# Anemometer.net
KiCad netlist of a schematic drawn in EAGLE
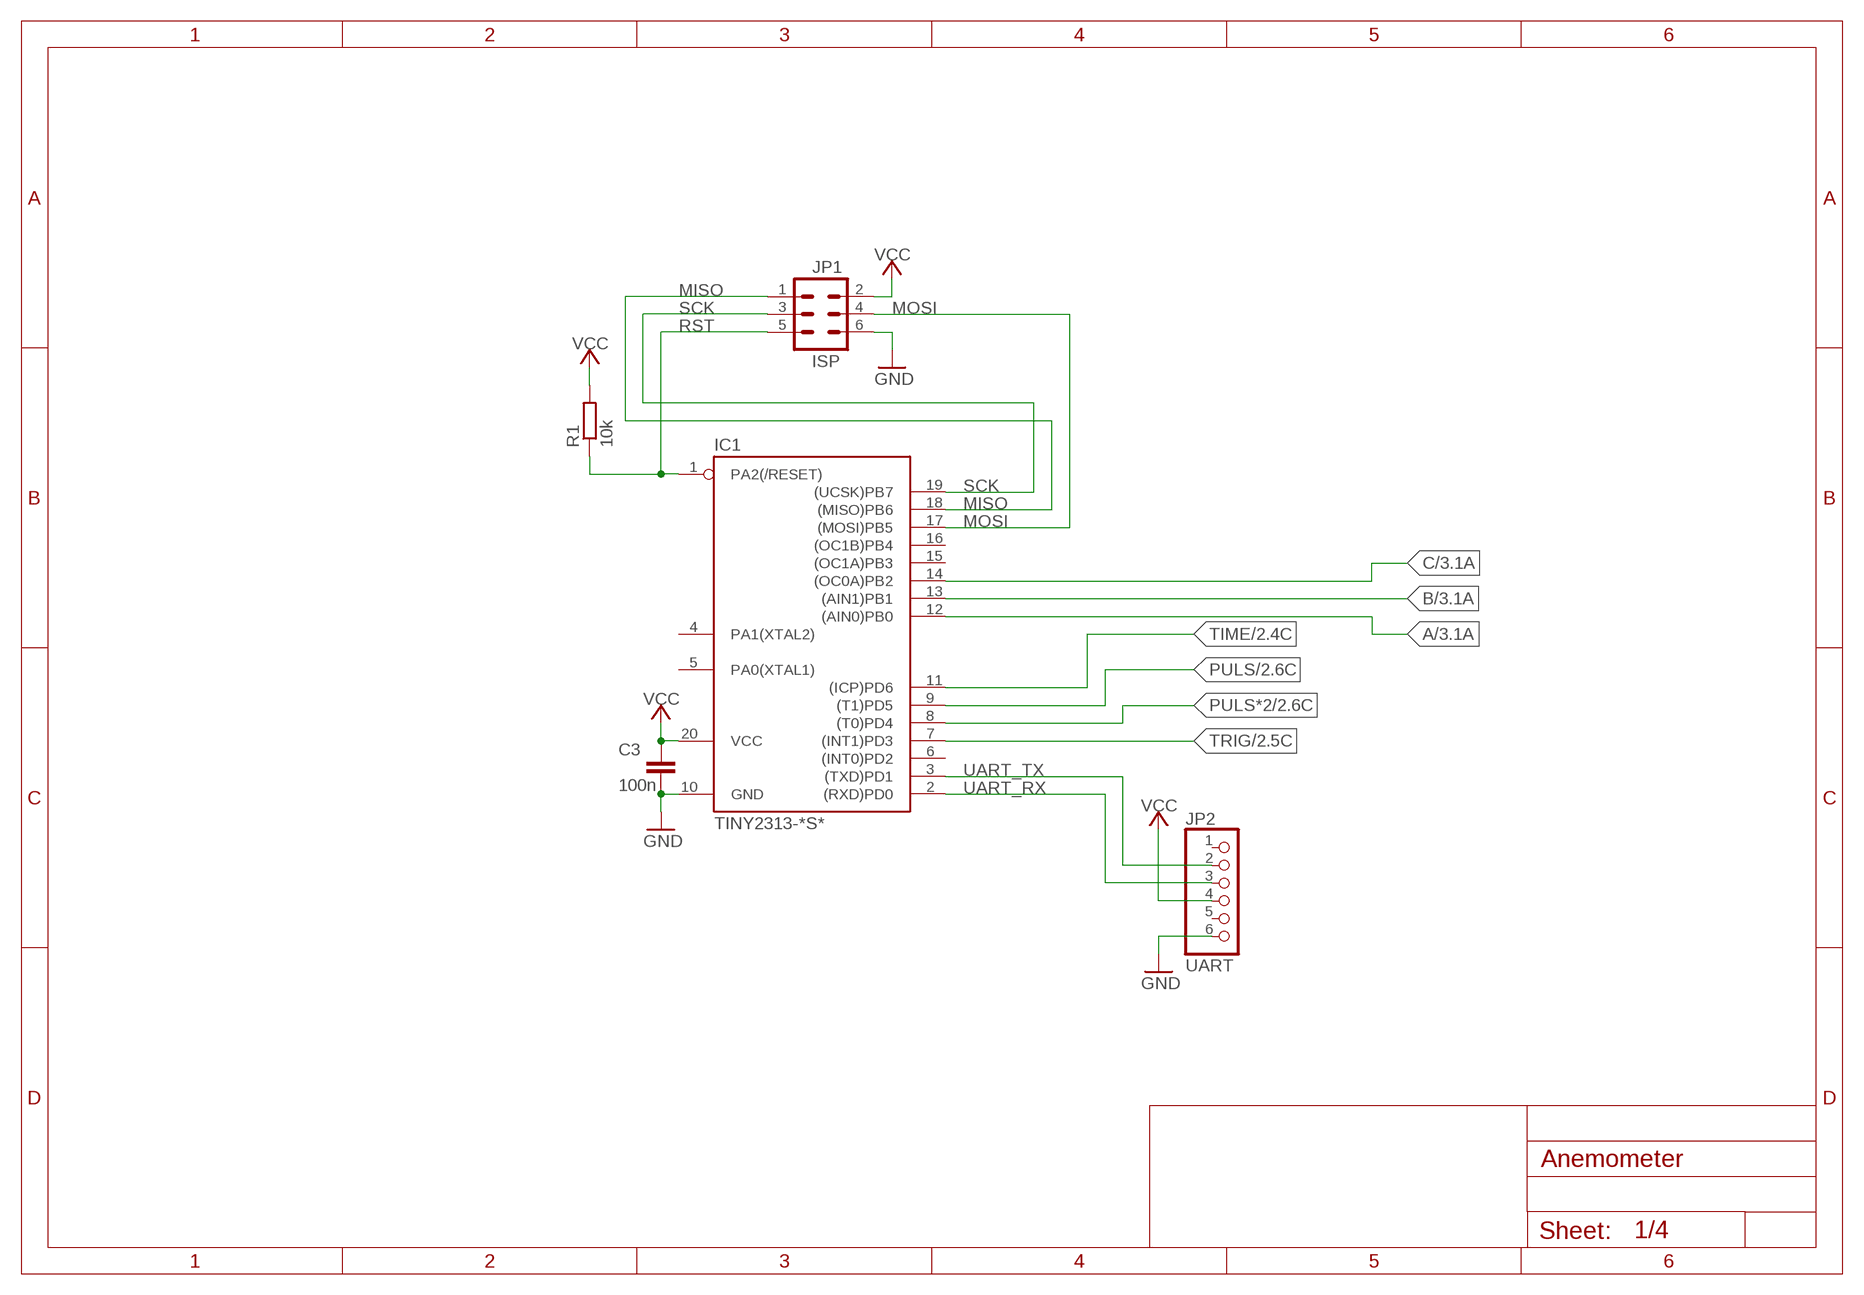
[diagram p0: schematic, sheet 1]
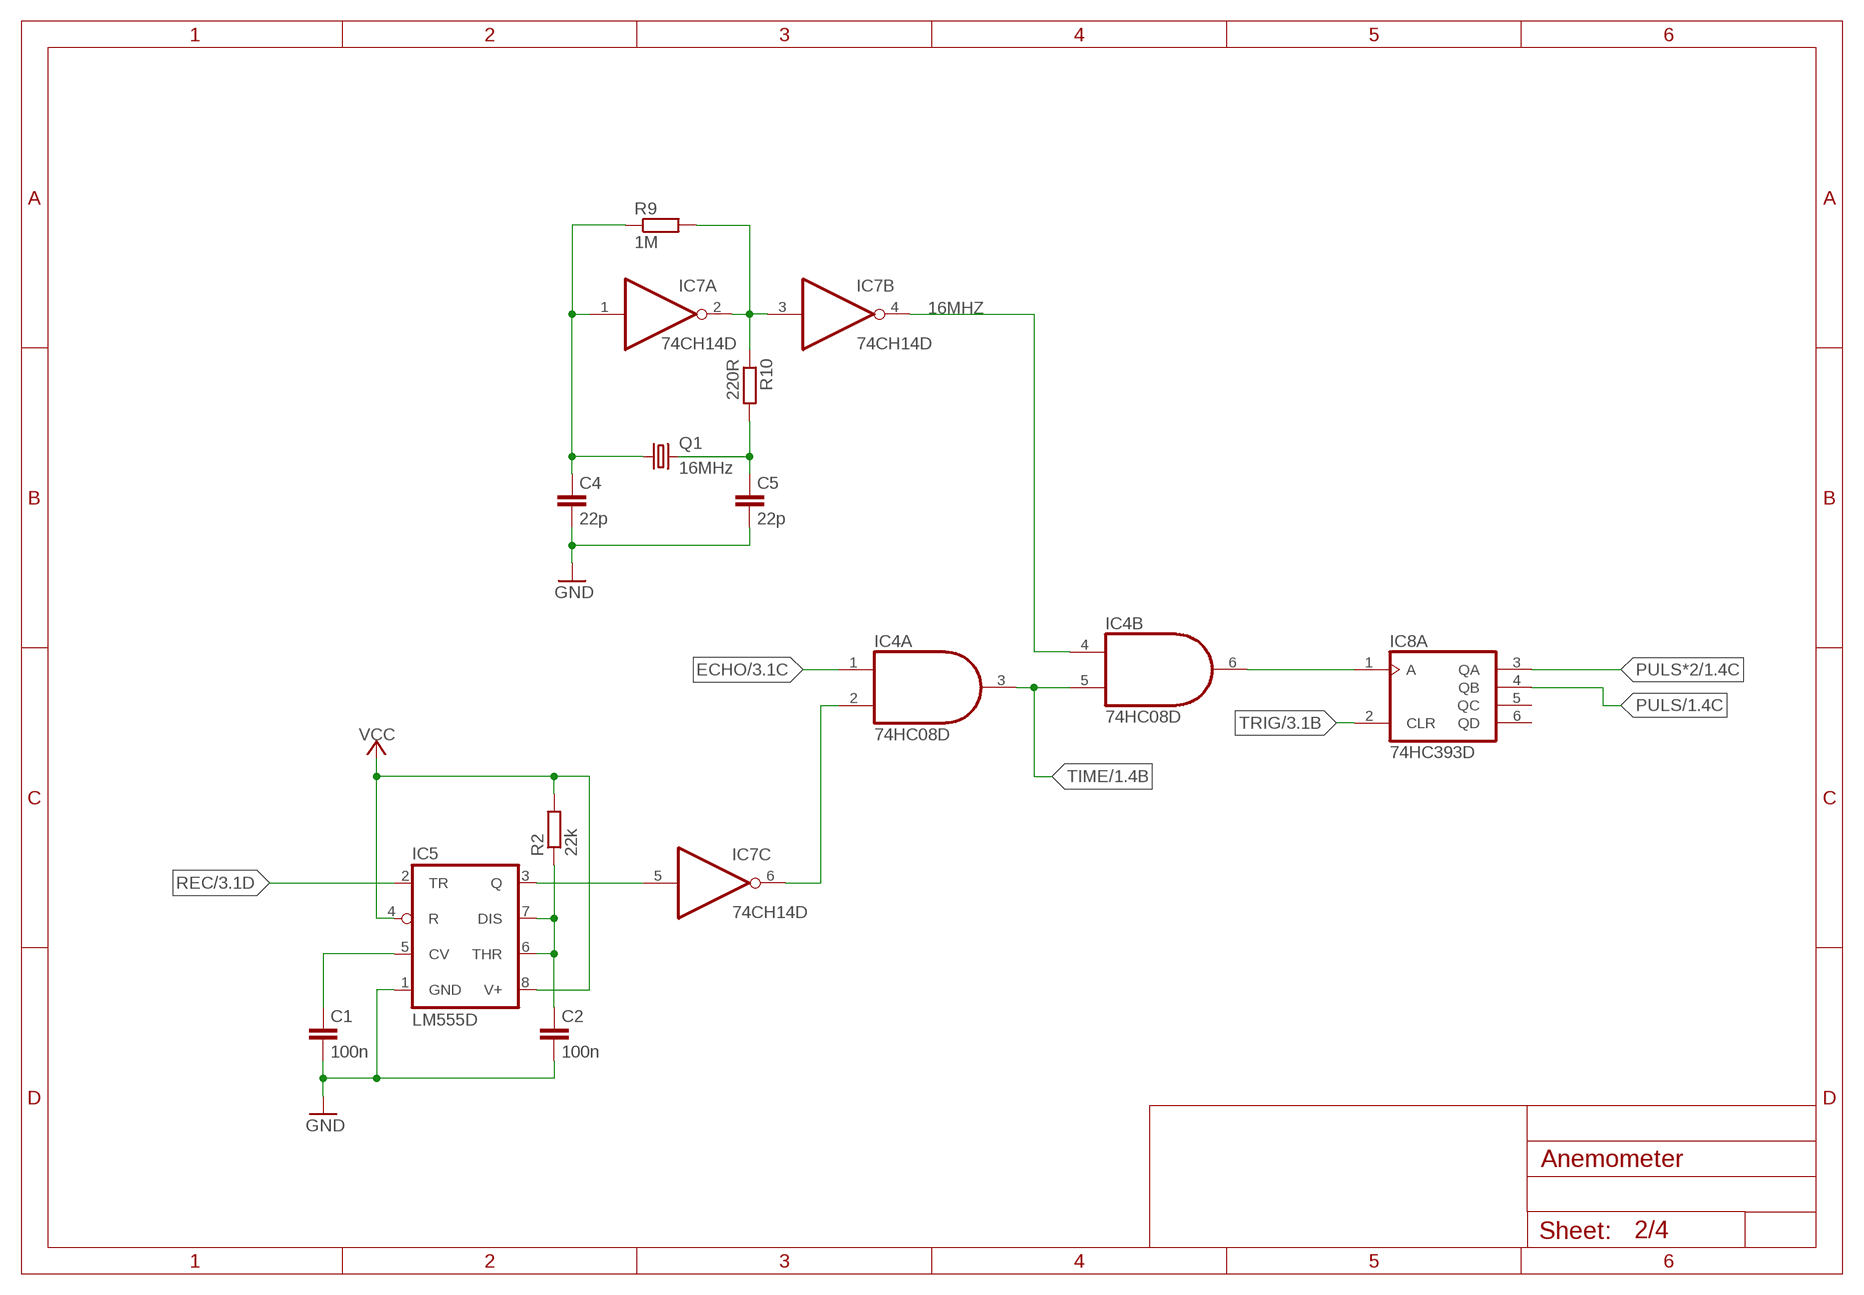
[diagram p1: schematic, sheet 2]
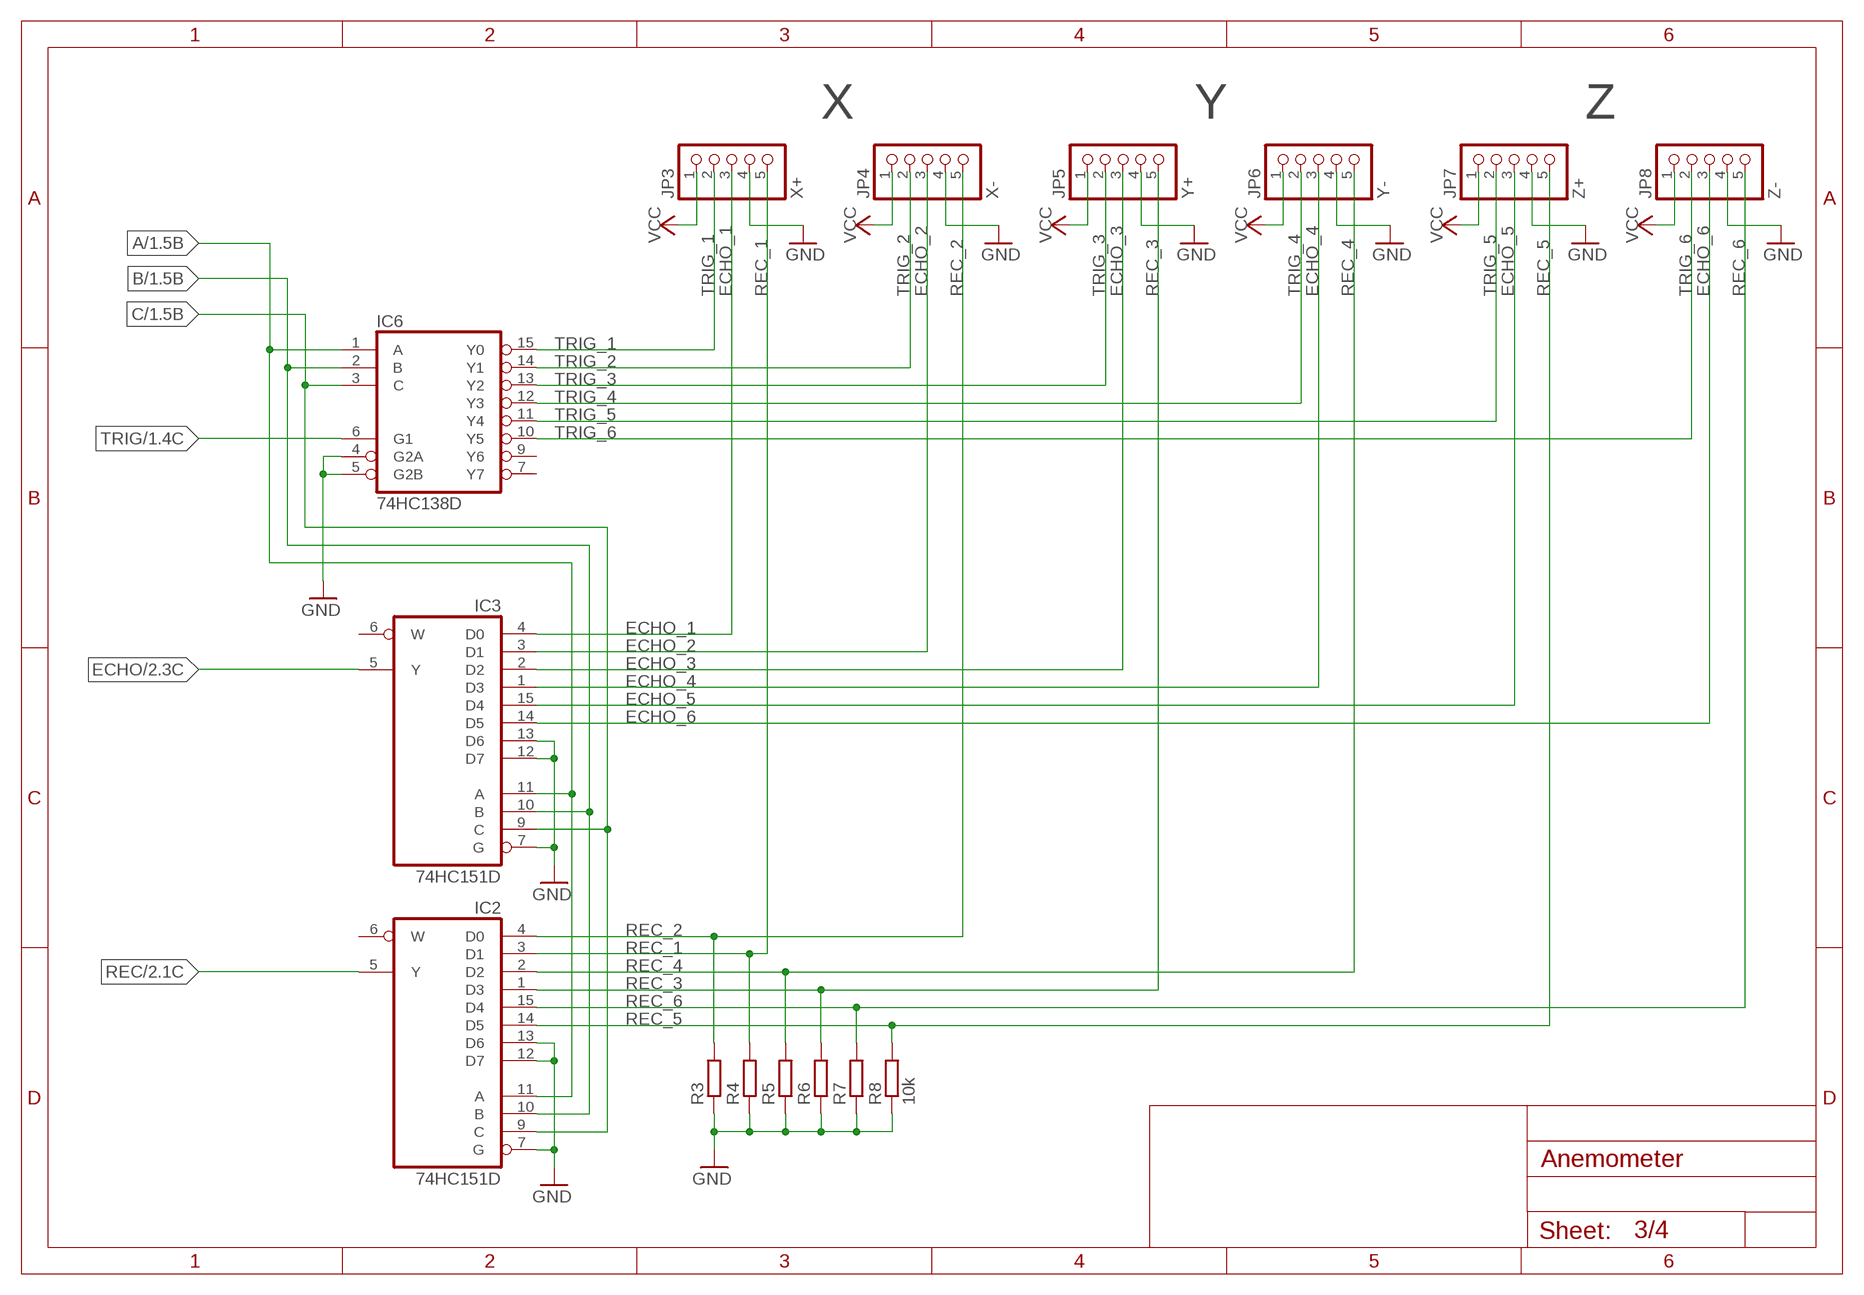
[diagram p2: schematic, sheet 3]
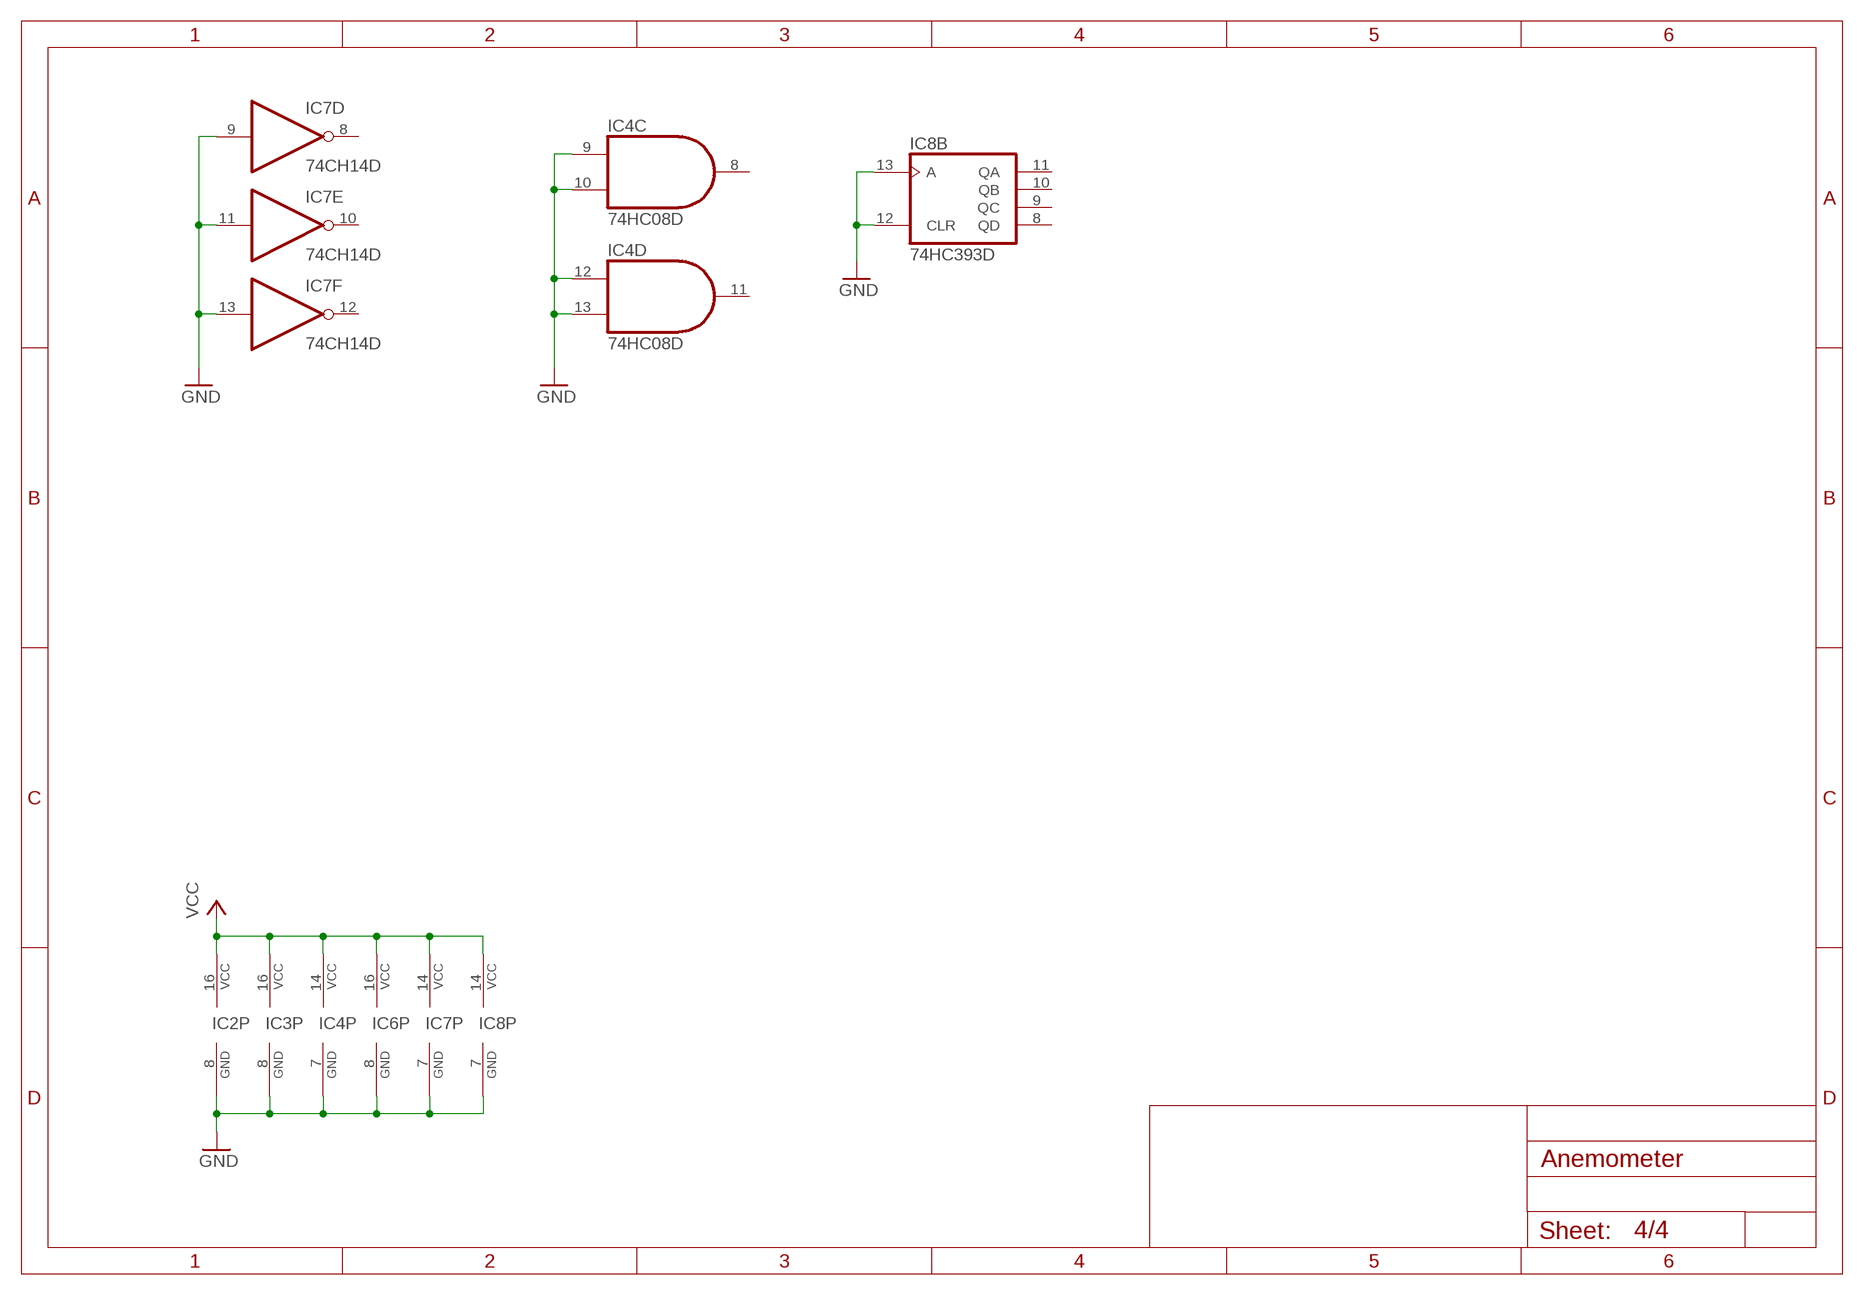
[diagram p3: schematic, sheet 4]

(export (version "E")
  (design (tool "Eeschema 10.0.6"))
  (components
    (comp (ref "C1")
      (value "100n")
      (footprint "eagle-import:C0805")
      (libsource (lib "eagle-import") (part "C-EUC0805"))
    )
    (comp (ref "C2")
      (value "100n")
      (footprint "eagle-import:C0805")
      (libsource (lib "eagle-import") (part "C-EUC0805"))
    )
    (comp (ref "C4")
      (value "22p")
      (footprint "eagle-import:C0805")
      (libsource (lib "eagle-import") (part "C-EUC0805"))
    )
    (comp (ref "C5")
      (value "22p")
      (footprint "eagle-import:C0805")
      (libsource (lib "eagle-import") (part "C-EUC0805"))
    )
    (comp (ref "IC4")
      (value "74HC08D")
      (footprint "eagle-import:SO14")
      (libsource (lib "eagle-import") (part "7408DALS"))
    )
    (comp (ref "IC5")
      (value "LM555D")
      (footprint "eagle-import:SO08")
      (libsource (lib "eagle-import") (part "555DLM"))
    )
    (comp (ref "IC7")
      (value "74CH14D")
      (footprint "eagle-import:SO14")
      (libsource (lib "eagle-import") (part "7404DALS"))
    )
    (comp (ref "IC8")
      (value "74HC393D")
      (footprint "eagle-import:SO14")
      (libsource (lib "eagle-import") (part "74393DLS"))
    )
    (comp (ref "Q1")
      (value "16MHz")
      (footprint "eagle-import:HC49UP")
      (libsource (lib "eagle-import") (part "CRYSTALHC49UP"))
    )
    (comp (ref "R2")
      (value "22k")
      (footprint "eagle-import:R0805")
      (libsource (lib "eagle-import") (part "R-EU_R0805"))
    )
    (comp (ref "R9")
      (value "1M")
      (footprint "eagle-import:R0805")
      (libsource (lib "eagle-import") (part "R-EU_R0805"))
    )
    (comp (ref "R10")
      (value "220R")
      (footprint "eagle-import:R0805")
      (libsource (lib "eagle-import") (part "R-EU_R0805"))
    )
    (comp (ref "IC2")
      (value "74HC151D")
      (footprint "eagle-import:SO16")
      (libsource (lib "eagle-import") (part "74151DLS"))
    )
    (comp (ref "IC3")
      (value "74HC151D")
      (footprint "eagle-import:SO16")
      (libsource (lib "eagle-import") (part "74151DLS"))
    )
    (comp (ref "IC6")
      (value "74HC138D")
      (footprint "eagle-import:SO16")
      (libsource (lib "eagle-import") (part "74138DLS"))
    )
    (comp (ref "JP3")
      (value "X+")
      (footprint "eagle-import:1X05")
      (libsource (lib "eagle-import") (part "PINHD-1X5"))
    )
    (comp (ref "JP4")
      (value "X-")
      (footprint "eagle-import:1X05")
      (libsource (lib "eagle-import") (part "PINHD-1X5"))
    )
    (comp (ref "JP5")
      (value "Y+")
      (footprint "eagle-import:1X05")
      (libsource (lib "eagle-import") (part "PINHD-1X5"))
    )
    (comp (ref "JP6")
      (value "Y-")
      (footprint "eagle-import:1X05")
      (libsource (lib "eagle-import") (part "PINHD-1X5"))
    )
    (comp (ref "JP7")
      (value "Z+")
      (footprint "eagle-import:1X05")
      (libsource (lib "eagle-import") (part "PINHD-1X5"))
    )
    (comp (ref "JP8")
      (value "Z-")
      (footprint "eagle-import:1X05")
      (libsource (lib "eagle-import") (part "PINHD-1X5"))
    )
    (comp (ref "R3")
      (value "10k")
      (footprint "eagle-import:R0805")
      (libsource (lib "eagle-import") (part "R-EU_R0805"))
    )
    (comp (ref "R4")
      (value "10k")
      (footprint "eagle-import:R0805")
      (libsource (lib "eagle-import") (part "R-EU_R0805"))
    )
    (comp (ref "R5")
      (value "10k")
      (footprint "eagle-import:R0805")
      (libsource (lib "eagle-import") (part "R-EU_R0805"))
    )
    (comp (ref "R6")
      (value "10k")
      (footprint "eagle-import:R0805")
      (libsource (lib "eagle-import") (part "R-EU_R0805"))
    )
    (comp (ref "R7")
      (value "10k")
      (footprint "eagle-import:R0805")
      (libsource (lib "eagle-import") (part "R-EU_R0805"))
    )
    (comp (ref "R8")
      (value "10k")
      (footprint "eagle-import:R0805")
      (libsource (lib "eagle-import") (part "R-EU_R0805"))
    )
    (comp (ref "C3")
      (value "100n")
      (footprint "eagle-import:C050-024X044")
      (libsource (lib "eagle-import") (part "C-EU050-024X044"))
    )
    (comp (ref "IC1")
      (value "TINY2313-*S*")
      (footprint "eagle-import:SO20L$")
      (libsource (lib "eagle-import") (part "TINY2313-S"))
    )
    (comp (ref "JP1")
      (value "ISP")
      (footprint "eagle-import:ML6")
      (libsource (lib "eagle-import") (part "ML6"))
    )
    (comp (ref "JP2")
      (value "UART")
      (footprint "eagle-import:1X06")
      (libsource (lib "eagle-import") (part "PINHD-1X6"))
    )
    (comp (ref "R1")
      (value "10k")
      (footprint "eagle-import:0207_10")
      (libsource (lib "eagle-import") (part "R-EU_0207/10"))
    )
  )
  (nets
    (net (code "1") (name "16MHZ") (class "Default")
      (node (ref "IC4") (pin "4") (pinfunction "I0_4") (pintype "input"))
      (node (ref "IC7") (pin "4") (pinfunction "O_4") (pintype "output"))
    )
    (net (code "2") (name "A") (class "Default")
      (node (ref "IC1") (pin "12") (pinfunction "(AIN0)PB0_12") (pintype "bidirectional"))
      (node (ref "IC2") (pin "11") (pinfunction "A_11") (pintype "input"))
      (node (ref "IC3") (pin "11") (pinfunction "A_11") (pintype "input"))
      (node (ref "IC6") (pin "1") (pinfunction "A_1") (pintype "input"))
    )
    (net (code "3") (name "B") (class "Default")
      (node (ref "IC1") (pin "13") (pinfunction "(AIN1)PB1_13") (pintype "bidirectional"))
      (node (ref "IC2") (pin "10") (pinfunction "B_10") (pintype "input"))
      (node (ref "IC3") (pin "10") (pinfunction "B_10") (pintype "input"))
      (node (ref "IC6") (pin "2") (pinfunction "B_2") (pintype "input"))
    )
    (net (code "4") (name "C") (class "Default")
      (node (ref "IC1") (pin "14") (pinfunction "(OC0A)PB2_14") (pintype "bidirectional"))
      (node (ref "IC2") (pin "9") (pinfunction "C_9") (pintype "input"))
      (node (ref "IC3") (pin "9") (pinfunction "C_9") (pintype "input"))
      (node (ref "IC6") (pin "3") (pinfunction "C_3") (pintype "input"))
    )
    (net (code "5") (name "ECHO") (class "Default")
      (node (ref "IC3") (pin "5") (pinfunction "Y_5") (pintype "output"))
      (node (ref "IC4") (pin "1") (pinfunction "I0_1") (pintype "input"))
    )
    (net (code "6") (name "ECHO_1") (class "Default")
      (node (ref "IC3") (pin "4") (pinfunction "D0_4") (pintype "input"))
      (node (ref "JP3") (pin "3") (pinfunction "3_3") (pintype "passive"))
    )
    (net (code "7") (name "ECHO_2") (class "Default")
      (node (ref "IC3") (pin "3") (pinfunction "D1_3") (pintype "input"))
      (node (ref "JP4") (pin "3") (pinfunction "3_3") (pintype "passive"))
    )
    (net (code "8") (name "ECHO_3") (class "Default")
      (node (ref "IC3") (pin "2") (pinfunction "D2_2") (pintype "input"))
      (node (ref "JP5") (pin "3") (pinfunction "3_3") (pintype "passive"))
    )
    (net (code "9") (name "ECHO_4") (class "Default")
      (node (ref "IC3") (pin "1") (pinfunction "D3_1") (pintype "input"))
      (node (ref "JP6") (pin "3") (pinfunction "3_3") (pintype "passive"))
    )
    (net (code "10") (name "ECHO_5") (class "Default")
      (node (ref "IC3") (pin "15") (pinfunction "D4_15") (pintype "input"))
      (node (ref "JP7") (pin "3") (pinfunction "3_3") (pintype "passive"))
    )
    (net (code "11") (name "ECHO_6") (class "Default")
      (node (ref "IC3") (pin "14") (pinfunction "D5_14") (pintype "input"))
      (node (ref "JP8") (pin "3") (pinfunction "3_3") (pintype "passive"))
    )
    (net (code "12") (name "GND") (class "Default")
      (node (ref "C1") (pin "2") (pinfunction "2_2") (pintype "passive"))
      (node (ref "C2") (pin "2") (pinfunction "2_2") (pintype "passive"))
      (node (ref "C3") (pin "2") (pinfunction "2_2") (pintype "passive"))
      (node (ref "C4") (pin "2") (pinfunction "2_2") (pintype "passive"))
      (node (ref "C5") (pin "2") (pinfunction "2_2") (pintype "passive"))
      (node (ref "IC1") (pin "10") (pinfunction "GND_10") (pintype "power_in"))
      (node (ref "IC2") (pin "12") (pinfunction "D7_12") (pintype "input"))
      (node (ref "IC2") (pin "13") (pinfunction "D6_13") (pintype "input"))
      (node (ref "IC2") (pin "7") (pinfunction "G_7") (pintype "input"))
      (node (ref "IC2") (pin "8") (pinfunction "GND_8") (pintype "power_in"))
      (node (ref "IC3") (pin "12") (pinfunction "D7_12") (pintype "input"))
      (node (ref "IC3") (pin "13") (pinfunction "D6_13") (pintype "input"))
      (node (ref "IC3") (pin "7") (pinfunction "G_7") (pintype "input"))
      (node (ref "IC3") (pin "8") (pinfunction "GND_8") (pintype "power_in"))
      (node (ref "IC4") (pin "10") (pinfunction "I1_10") (pintype "input"))
      (node (ref "IC4") (pin "12") (pinfunction "I0_12") (pintype "input"))
      (node (ref "IC4") (pin "13") (pinfunction "I1_13") (pintype "input"))
      (node (ref "IC4") (pin "7") (pinfunction "GND_7") (pintype "power_in"))
      (node (ref "IC4") (pin "9") (pinfunction "I0_9") (pintype "input"))
      (node (ref "IC5") (pin "1") (pinfunction "GND_1") (pintype "power_in"))
      (node (ref "IC6") (pin "4") (pinfunction "G2A_4") (pintype "input"))
      (node (ref "IC6") (pin "5") (pinfunction "G2B_5") (pintype "input"))
      (node (ref "IC6") (pin "8") (pinfunction "GND_8") (pintype "power_in"))
      (node (ref "IC7") (pin "11") (pinfunction "I_11") (pintype "input"))
      (node (ref "IC7") (pin "13") (pinfunction "I_13") (pintype "input"))
      (node (ref "IC7") (pin "7") (pinfunction "GND_7") (pintype "power_in"))
      (node (ref "IC7") (pin "9") (pinfunction "I_9") (pintype "input"))
      (node (ref "IC8") (pin "12") (pinfunction "CLR_12") (pintype "input"))
      (node (ref "IC8") (pin "13") (pinfunction "A_13") (pintype "input"))
      (node (ref "IC8") (pin "7") (pinfunction "GND_7") (pintype "power_in"))
      (node (ref "JP1") (pin "6") (pinfunction "6_6") (pintype "passive"))
      (node (ref "JP2") (pin "6") (pinfunction "6_6") (pintype "passive"))
      (node (ref "JP3") (pin "4") (pinfunction "4_4") (pintype "passive"))
      (node (ref "JP4") (pin "4") (pinfunction "4_4") (pintype "passive"))
      (node (ref "JP5") (pin "4") (pinfunction "4_4") (pintype "passive"))
      (node (ref "JP6") (pin "4") (pinfunction "4_4") (pintype "passive"))
      (node (ref "JP7") (pin "4") (pinfunction "4_4") (pintype "passive"))
      (node (ref "JP8") (pin "4") (pinfunction "4_4") (pintype "passive"))
      (node (ref "R3") (pin "1") (pinfunction "1_1") (pintype "passive"))
      (node (ref "R4") (pin "1") (pinfunction "1_1") (pintype "passive"))
      (node (ref "R5") (pin "1") (pinfunction "1_1") (pintype "passive"))
      (node (ref "R6") (pin "1") (pinfunction "1_1") (pintype "passive"))
      (node (ref "R7") (pin "1") (pinfunction "1_1") (pintype "passive"))
      (node (ref "R8") (pin "1") (pinfunction "1_1") (pintype "passive"))
    )
    (net (code "13") (name "MISO") (class "Default")
      (node (ref "IC1") (pin "18") (pinfunction "(MISO)PB6_18") (pintype "bidirectional"))
      (node (ref "JP1") (pin "1") (pinfunction "1_1") (pintype "passive"))
    )
    (net (code "14") (name "MOSI") (class "Default")
      (node (ref "IC1") (pin "17") (pinfunction "(MOSI)PB5_17") (pintype "bidirectional"))
      (node (ref "JP1") (pin "4") (pinfunction "4_4") (pintype "passive"))
    )
    (net (code "15") (name "Net-(C5-Pad1)") (class "Default")
      (node (ref "C5") (pin "1") (pinfunction "1_1") (pintype "passive"))
      (node (ref "Q1") (pin "2") (pinfunction "2_2") (pintype "passive"))
      (node (ref "R10") (pin "2") (pinfunction "2_2") (pintype "passive"))
    )
    (net (code "16") (name "Net-(IC4A-I1)") (class "Default")
      (node (ref "IC4") (pin "2") (pinfunction "I1_2") (pintype "input"))
      (node (ref "IC7") (pin "6") (pinfunction "O_6") (pintype "output"))
    )
    (net (code "17") (name "Net-(IC4B-O)") (class "Default")
      (node (ref "IC4") (pin "6") (pinfunction "O_6") (pintype "output"))
      (node (ref "IC8") (pin "1") (pinfunction "A_1") (pintype "input"))
    )
    (net (code "18") (name "Net-(IC5-CV)") (class "Default")
      (node (ref "C1") (pin "1") (pinfunction "1_1") (pintype "passive"))
      (node (ref "IC5") (pin "5") (pinfunction "CV_5") (pintype "input"))
    )
    (net (code "19") (name "Net-(IC5-DIS)") (class "Default")
      (node (ref "C2") (pin "1") (pinfunction "1_1") (pintype "passive"))
      (node (ref "IC5") (pin "6") (pinfunction "THR_6") (pintype "input"))
      (node (ref "IC5") (pin "7") (pinfunction "DIS_7") (pintype "input"))
      (node (ref "R2") (pin "1") (pinfunction "1_1") (pintype "passive"))
    )
    (net (code "20") (name "Net-(IC5-Q)") (class "Default")
      (node (ref "IC5") (pin "3") (pinfunction "Q_3") (pintype "output"))
      (node (ref "IC7") (pin "5") (pinfunction "I_5") (pintype "input"))
    )
    (net (code "21") (name "Net-(IC7A-I)") (class "Default")
      (node (ref "C4") (pin "1") (pinfunction "1_1") (pintype "passive"))
      (node (ref "IC7") (pin "1") (pinfunction "I_1") (pintype "input"))
      (node (ref "Q1") (pin "1") (pinfunction "1_1") (pintype "passive"))
      (node (ref "R9") (pin "1") (pinfunction "1_1") (pintype "passive"))
    )
    (net (code "22") (name "Net-(IC7A-O)") (class "Default")
      (node (ref "IC7") (pin "2") (pinfunction "O_2") (pintype "output"))
      (node (ref "IC7") (pin "3") (pinfunction "I_3") (pintype "input"))
      (node (ref "R10") (pin "1") (pinfunction "1_1") (pintype "passive"))
      (node (ref "R9") (pin "2") (pinfunction "2_2") (pintype "passive"))
    )
    (net (code "23") (name "PULS") (class "Default")
      (node (ref "IC1") (pin "9") (pinfunction "(T1)PD5_9") (pintype "bidirectional"))
      (node (ref "IC8") (pin "4") (pinfunction "QB_4") (pintype "output"))
    )
    (net (code "24") (name "PULS*2") (class "Default")
      (node (ref "IC1") (pin "8") (pinfunction "(T0)PD4_8") (pintype "bidirectional"))
      (node (ref "IC8") (pin "3") (pinfunction "QA_3") (pintype "output"))
    )
    (net (code "25") (name "REC") (class "Default")
      (node (ref "IC2") (pin "5") (pinfunction "Y_5") (pintype "output"))
      (node (ref "IC5") (pin "2") (pinfunction "TR_2") (pintype "input"))
    )
    (net (code "26") (name "REC_1") (class "Default")
      (node (ref "IC2") (pin "3") (pinfunction "D1_3") (pintype "input"))
      (node (ref "JP3") (pin "5") (pinfunction "5_5") (pintype "passive"))
      (node (ref "R4") (pin "2") (pinfunction "2_2") (pintype "passive"))
    )
    (net (code "27") (name "REC_2") (class "Default")
      (node (ref "IC2") (pin "4") (pinfunction "D0_4") (pintype "input"))
      (node (ref "JP4") (pin "5") (pinfunction "5_5") (pintype "passive"))
      (node (ref "R3") (pin "2") (pinfunction "2_2") (pintype "passive"))
    )
    (net (code "28") (name "REC_3") (class "Default")
      (node (ref "IC2") (pin "1") (pinfunction "D3_1") (pintype "input"))
      (node (ref "JP5") (pin "5") (pinfunction "5_5") (pintype "passive"))
      (node (ref "R6") (pin "2") (pinfunction "2_2") (pintype "passive"))
    )
    (net (code "29") (name "REC_4") (class "Default")
      (node (ref "IC2") (pin "2") (pinfunction "D2_2") (pintype "input"))
      (node (ref "JP6") (pin "5") (pinfunction "5_5") (pintype "passive"))
      (node (ref "R5") (pin "2") (pinfunction "2_2") (pintype "passive"))
    )
    (net (code "30") (name "REC_5") (class "Default")
      (node (ref "IC2") (pin "14") (pinfunction "D5_14") (pintype "input"))
      (node (ref "JP7") (pin "5") (pinfunction "5_5") (pintype "passive"))
      (node (ref "R8") (pin "2") (pinfunction "2_2") (pintype "passive"))
    )
    (net (code "31") (name "REC_6") (class "Default")
      (node (ref "IC2") (pin "15") (pinfunction "D4_15") (pintype "input"))
      (node (ref "JP8") (pin "5") (pinfunction "5_5") (pintype "passive"))
      (node (ref "R7") (pin "2") (pinfunction "2_2") (pintype "passive"))
    )
    (net (code "32") (name "RST") (class "Default")
      (node (ref "IC1") (pin "1") (pinfunction "PA2(/RESET)_1") (pintype "input"))
      (node (ref "JP1") (pin "5") (pinfunction "5_5") (pintype "passive"))
      (node (ref "R1") (pin "1") (pinfunction "1_1") (pintype "passive"))
    )
    (net (code "33") (name "SCK") (class "Default")
      (node (ref "IC1") (pin "19") (pinfunction "(UCSK)PB7_19") (pintype "bidirectional"))
      (node (ref "JP1") (pin "3") (pinfunction "3_3") (pintype "passive"))
    )
    (net (code "34") (name "TIME") (class "Default")
      (node (ref "IC1") (pin "11") (pinfunction "(ICP)PD6_11") (pintype "bidirectional"))
      (node (ref "IC4") (pin "3") (pinfunction "O_3") (pintype "output"))
      (node (ref "IC4") (pin "5") (pinfunction "I1_5") (pintype "input"))
    )
    (net (code "35") (name "TRIG") (class "Default")
      (node (ref "IC1") (pin "7") (pinfunction "(INT1)PD3_7") (pintype "bidirectional"))
      (node (ref "IC6") (pin "6") (pinfunction "G1_6") (pintype "input"))
      (node (ref "IC8") (pin "2") (pinfunction "CLR_2") (pintype "input"))
    )
    (net (code "36") (name "TRIG_1") (class "Default")
      (node (ref "IC6") (pin "15") (pinfunction "Y0_15") (pintype "output"))
      (node (ref "JP3") (pin "2") (pinfunction "2_2") (pintype "passive"))
    )
    (net (code "37") (name "TRIG_2") (class "Default")
      (node (ref "IC6") (pin "14") (pinfunction "Y1_14") (pintype "output"))
      (node (ref "JP4") (pin "2") (pinfunction "2_2") (pintype "passive"))
    )
    (net (code "38") (name "TRIG_3") (class "Default")
      (node (ref "IC6") (pin "13") (pinfunction "Y2_13") (pintype "output"))
      (node (ref "JP5") (pin "2") (pinfunction "2_2") (pintype "passive"))
    )
    (net (code "39") (name "TRIG_4") (class "Default")
      (node (ref "IC6") (pin "12") (pinfunction "Y3_12") (pintype "output"))
      (node (ref "JP6") (pin "2") (pinfunction "2_2") (pintype "passive"))
    )
    (net (code "40") (name "TRIG_5") (class "Default")
      (node (ref "IC6") (pin "11") (pinfunction "Y4_11") (pintype "output"))
      (node (ref "JP7") (pin "2") (pinfunction "2_2") (pintype "passive"))
    )
    (net (code "41") (name "TRIG_6") (class "Default")
      (node (ref "IC6") (pin "10") (pinfunction "Y5_10") (pintype "output"))
      (node (ref "JP8") (pin "2") (pinfunction "2_2") (pintype "passive"))
    )
    (net (code "42") (name "UART_RX") (class "Default")
      (node (ref "IC1") (pin "2") (pinfunction "(RXD)PD0_2") (pintype "bidirectional"))
      (node (ref "JP2") (pin "3") (pinfunction "3_3") (pintype "passive"))
    )
    (net (code "43") (name "UART_TX") (class "Default")
      (node (ref "IC1") (pin "3") (pinfunction "(TXD)PD1_3") (pintype "bidirectional"))
      (node (ref "JP2") (pin "2") (pinfunction "2_2") (pintype "passive"))
    )
    (net (code "44") (name "VCC") (class "Default")
      (node (ref "C3") (pin "1") (pinfunction "1_1") (pintype "passive"))
      (node (ref "IC1") (pin "20") (pinfunction "VCC_20") (pintype "power_in"))
      (node (ref "IC2") (pin "16") (pinfunction "VCC_16") (pintype "power_in"))
      (node (ref "IC3") (pin "16") (pinfunction "VCC_16") (pintype "power_in"))
      (node (ref "IC4") (pin "14") (pinfunction "VCC_14") (pintype "power_in"))
      (node (ref "IC5") (pin "4") (pinfunction "R_4") (pintype "input"))
      (node (ref "IC5") (pin "8") (pinfunction "V+_8") (pintype "power_in"))
      (node (ref "IC6") (pin "16") (pinfunction "VCC_16") (pintype "power_in"))
      (node (ref "IC7") (pin "14") (pinfunction "VCC_14") (pintype "power_in"))
      (node (ref "IC8") (pin "14") (pinfunction "VCC_14") (pintype "power_in"))
      (node (ref "JP1") (pin "2") (pinfunction "2_2") (pintype "passive"))
      (node (ref "JP2") (pin "4") (pinfunction "4_4") (pintype "passive"))
      (node (ref "JP3") (pin "1") (pinfunction "1_1") (pintype "passive"))
      (node (ref "JP4") (pin "1") (pinfunction "1_1") (pintype "passive"))
      (node (ref "JP5") (pin "1") (pinfunction "1_1") (pintype "passive"))
      (node (ref "JP6") (pin "1") (pinfunction "1_1") (pintype "passive"))
      (node (ref "JP7") (pin "1") (pinfunction "1_1") (pintype "passive"))
      (node (ref "JP8") (pin "1") (pinfunction "1_1") (pintype "passive"))
      (node (ref "R1") (pin "2") (pinfunction "2_2") (pintype "passive"))
      (node (ref "R2") (pin "2") (pinfunction "2_2") (pintype "passive"))
    )
    (net (code "45") (name "unconnected-(IC1-(INT0)PD2-Pad6)") (class "Default")
      (node (ref "IC1") (pin "6") (pinfunction "(INT0)PD2_6") (pintype "bidirectional"))
    )
    (net (code "46") (name "unconnected-(IC1-(OC1A)PB3-Pad15)") (class "Default")
      (node (ref "IC1") (pin "15") (pinfunction "(OC1A)PB3_15") (pintype "bidirectional"))
    )
    (net (code "47") (name "unconnected-(IC1-(OC1B)PB4-Pad16)") (class "Default")
      (node (ref "IC1") (pin "16") (pinfunction "(OC1B)PB4_16") (pintype "bidirectional"))
    )
    (net (code "48") (name "unconnected-(IC1-PA0(XTAL1)-Pad5)") (class "Default")
      (node (ref "IC1") (pin "5") (pinfunction "PA0(XTAL1)_5") (pintype "bidirectional"))
    )
    (net (code "49") (name "unconnected-(IC1-PA1(XTAL2)-Pad4)") (class "Default")
      (node (ref "IC1") (pin "4") (pinfunction "PA1(XTAL2)_4") (pintype "bidirectional"))
    )
    (net (code "50") (name "unconnected-(IC2A-W-Pad6)") (class "Default")
      (node (ref "IC2") (pin "6") (pinfunction "W_6") (pintype "output"))
    )
    (net (code "51") (name "unconnected-(IC3A-W-Pad6)") (class "Default")
      (node (ref "IC3") (pin "6") (pinfunction "W_6") (pintype "output"))
    )
    (net (code "52") (name "unconnected-(IC4C-O-Pad8)") (class "Default")
      (node (ref "IC4") (pin "8") (pinfunction "O_8") (pintype "output"))
    )
    (net (code "53") (name "unconnected-(IC4D-O-Pad11)") (class "Default")
      (node (ref "IC4") (pin "11") (pinfunction "O_11") (pintype "output"))
    )
    (net (code "54") (name "unconnected-(IC6A-Y6-Pad9)") (class "Default")
      (node (ref "IC6") (pin "9") (pinfunction "Y6_9") (pintype "output"))
    )
    (net (code "55") (name "unconnected-(IC6A-Y7-Pad7)") (class "Default")
      (node (ref "IC6") (pin "7") (pinfunction "Y7_7") (pintype "output"))
    )
    (net (code "56") (name "unconnected-(IC7D-O-Pad8)") (class "Default")
      (node (ref "IC7") (pin "8") (pinfunction "O_8") (pintype "output"))
    )
    (net (code "57") (name "unconnected-(IC7E-O-Pad10)") (class "Default")
      (node (ref "IC7") (pin "10") (pinfunction "O_10") (pintype "output"))
    )
    (net (code "58") (name "unconnected-(IC7F-O-Pad12)") (class "Default")
      (node (ref "IC7") (pin "12") (pinfunction "O_12") (pintype "output"))
    )
    (net (code "59") (name "unconnected-(IC8A-QC-Pad5)") (class "Default")
      (node (ref "IC8") (pin "5") (pinfunction "QC_5") (pintype "output"))
    )
    (net (code "60") (name "unconnected-(IC8A-QD-Pad6)") (class "Default")
      (node (ref "IC8") (pin "6") (pinfunction "QD_6") (pintype "output"))
    )
    (net (code "61") (name "unconnected-(IC8B-QA-Pad11)") (class "Default")
      (node (ref "IC8") (pin "11") (pinfunction "QA_11") (pintype "output"))
    )
    (net (code "62") (name "unconnected-(IC8B-QB-Pad10)") (class "Default")
      (node (ref "IC8") (pin "10") (pinfunction "QB_10") (pintype "output"))
    )
    (net (code "63") (name "unconnected-(IC8B-QC-Pad9)") (class "Default")
      (node (ref "IC8") (pin "9") (pinfunction "QC_9") (pintype "output"))
    )
    (net (code "64") (name "unconnected-(IC8B-QD-Pad8)") (class "Default")
      (node (ref "IC8") (pin "8") (pinfunction "QD_8") (pintype "output"))
    )
    (net (code "65") (name "unconnected-(JP2-Pad1)") (class "Default")
      (node (ref "JP2") (pin "1") (pinfunction "1_1") (pintype "passive"))
    )
    (net (code "66") (name "unconnected-(JP2-Pad5)") (class "Default")
      (node (ref "JP2") (pin "5") (pinfunction "5_5") (pintype "passive"))
    )
  )
)
